# Atlas.net
KiCad netlist of a schematic drawn in EAGLE
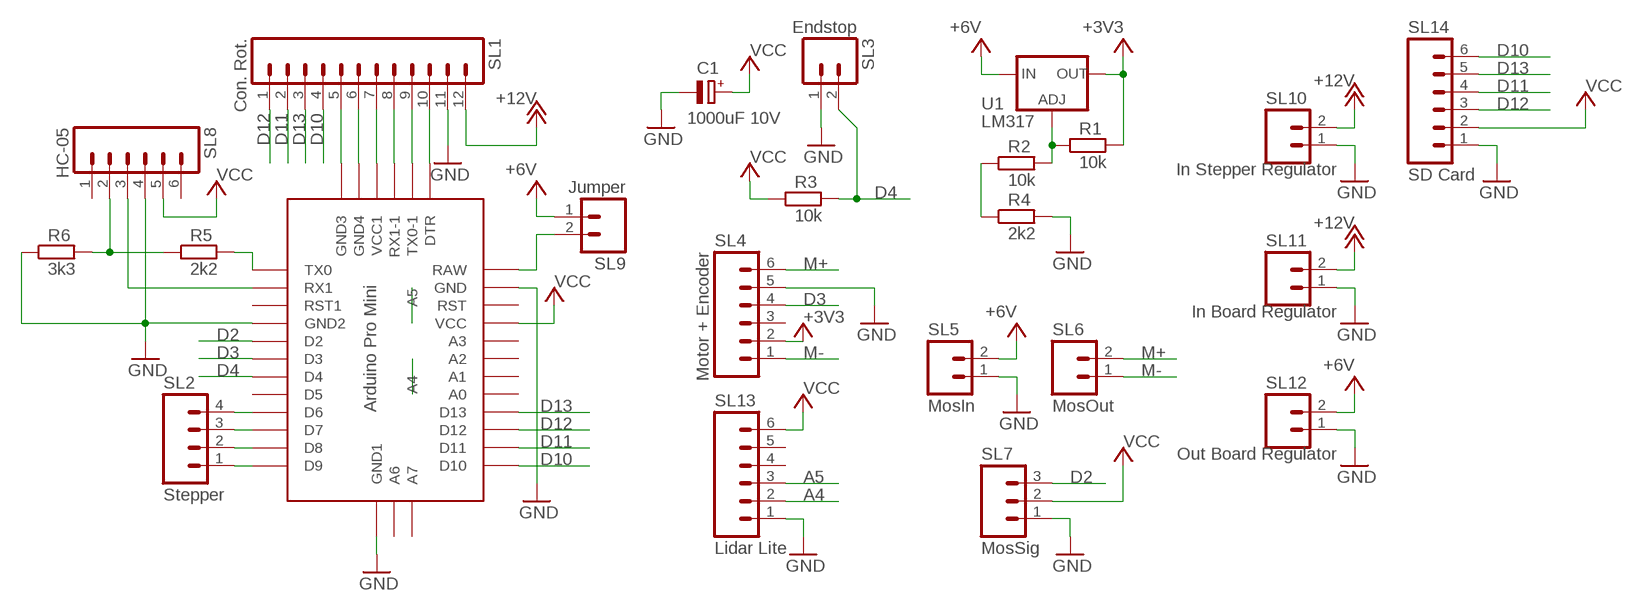
[diagram p0: schematic, sheet 1]

(export (version "E")
  (design (tool "Eeschema 10.0.6"))
  (components
    (comp (ref "C1")
      (value "1000uF 10V")
      (footprint "eagle-import:E5-10,5")
      (libsource (lib "eagle-import") (part "CPOL-EUE5-10.5"))
    )
    (comp (ref "R1")
      (value "10k")
      (footprint "eagle-import:0207_10")
      (libsource (lib "eagle-import") (part "R-EU_0207/10"))
    )
    (comp (ref "R2")
      (value "10k")
      (footprint "eagle-import:0207_10")
      (libsource (lib "eagle-import") (part "R-EU_0207/10"))
    )
    (comp (ref "R3")
      (value "10k")
      (footprint "eagle-import:0207_10")
      (libsource (lib "eagle-import") (part "R-EU_0207/10"))
    )
    (comp (ref "R4")
      (value "2k2")
      (footprint "eagle-import:0207_10")
      (libsource (lib "eagle-import") (part "R-EU_0207/10"))
    )
    (comp (ref "R5")
      (value "2k2")
      (footprint "eagle-import:0207_10")
      (libsource (lib "eagle-import") (part "R-EU_0207/10"))
    )
    (comp (ref "R6")
      (value "3k3")
      (footprint "eagle-import:0207_10")
      (libsource (lib "eagle-import") (part "R-EU_0207/10"))
    )
    (comp (ref "SL1")
      (value "Con. Rot.")
      (footprint "eagle-import:12P")
      (libsource (lib "eagle-import") (part "M12"))
    )
    (comp (ref "SL2")
      (value "Stepper")
      (footprint "eagle-import:04P")
      (libsource (lib "eagle-import") (part "M04"))
    )
    (comp (ref "SL3")
      (value "Endstop")
      (footprint "eagle-import:02P")
      (libsource (lib "eagle-import") (part "M02"))
    )
    (comp (ref "SL4")
      (value "Motor + Encoder")
      (footprint "eagle-import:06P")
      (libsource (lib "eagle-import") (part "M06"))
    )
    (comp (ref "SL5")
      (value "MosIn")
      (footprint "eagle-import:02P")
      (libsource (lib "eagle-import") (part "M02"))
    )
    (comp (ref "SL6")
      (value "MosOut")
      (footprint "eagle-import:02P")
      (libsource (lib "eagle-import") (part "M02"))
    )
    (comp (ref "SL7")
      (value "MosSig")
      (footprint "eagle-import:03P")
      (libsource (lib "eagle-import") (part "M03"))
    )
    (comp (ref "SL8")
      (value "HC-05")
      (footprint "eagle-import:06P")
      (libsource (lib "eagle-import") (part "M06"))
    )
    (comp (ref "SL9")
      (value "Jumper")
      (footprint "eagle-import:02P")
      (libsource (lib "eagle-import") (part "M02"))
    )
    (comp (ref "SL10")
      (value "In Stepper Regulator")
      (footprint "eagle-import:02P")
      (libsource (lib "eagle-import") (part "M02"))
    )
    (comp (ref "SL11")
      (value "In Board Regulator")
      (footprint "eagle-import:02P")
      (libsource (lib "eagle-import") (part "M02"))
    )
    (comp (ref "SL12")
      (value "Out Board Regulator")
      (footprint "eagle-import:02P")
      (libsource (lib "eagle-import") (part "M02"))
    )
    (comp (ref "SL13")
      (value "Lidar Lite")
      (footprint "eagle-import:06P")
      (libsource (lib "eagle-import") (part "M06"))
    )
    (comp (ref "SL14")
      (value "SD Card")
      (footprint "eagle-import:06P")
      (libsource (lib "eagle-import") (part "M06"))
    )
    (comp (ref "U$1")
      (value "ABK-PRO-MINI")
      (footprint "eagle-import:ABK-PRO-MINI")
      (libsource (lib "eagle-import") (part "ABK-PRO-MINI"))
    )
    (comp (ref "U1")
      (value "LM317")
      (footprint "eagle-import:TO220-ADJ")
      (libsource (lib "eagle-import") (part "V_REG_317SINK"))
    )
  )
  (nets
    (net (code "1") (name "+3V3") (class "Default")
      (node (ref "R1") (pin "2") (pinfunction "2_2") (pintype "passive"))
      (node (ref "SL4") (pin "2") (pinfunction "2_2") (pintype "passive"))
      (node (ref "U1") (pin "OUT") (pinfunction "OUT_OUT") (pintype "output"))
    )
    (net (code "2") (name "+6V") (class "Default")
      (node (ref "SL12") (pin "2") (pinfunction "2_2") (pintype "passive"))
      (node (ref "SL5") (pin "2") (pinfunction "2_2") (pintype "passive"))
      (node (ref "SL9") (pin "1") (pinfunction "1_1") (pintype "passive"))
      (node (ref "U1") (pin "IN") (pinfunction "IN_IN") (pintype "input"))
    )
    (net (code "3") (name "+12V") (class "Default")
      (node (ref "SL1") (pin "12") (pinfunction "12_12") (pintype "passive"))
      (node (ref "SL10") (pin "2") (pinfunction "2_2") (pintype "passive"))
      (node (ref "SL11") (pin "2") (pinfunction "2_2") (pintype "passive"))
    )
    (net (code "4") (name "/A4") (class "Default")
      (node (ref "SL13") (pin "2") (pinfunction "2_2") (pintype "passive"))
      (node (ref "U$1") (pin "A4") (pinfunction "A4_A4") (pintype "bidirectional"))
    )
    (net (code "5") (name "/A5") (class "Default")
      (node (ref "SL13") (pin "3") (pinfunction "3_3") (pintype "passive"))
      (node (ref "U$1") (pin "A5") (pinfunction "A5_A5") (pintype "bidirectional"))
    )
    (net (code "6") (name "/D2") (class "Default")
      (node (ref "SL7") (pin "3") (pinfunction "3_3") (pintype "passive"))
      (node (ref "U$1") (pin "D2") (pinfunction "D2_D2") (pintype "bidirectional"))
    )
    (net (code "7") (name "/D3") (class "Default")
      (node (ref "SL4") (pin "4") (pinfunction "4_4") (pintype "passive"))
      (node (ref "U$1") (pin "D3") (pinfunction "D3_D3") (pintype "bidirectional"))
    )
    (net (code "8") (name "/D4") (class "Default")
      (node (ref "R3") (pin "2") (pinfunction "2_2") (pintype "passive"))
      (node (ref "SL3") (pin "2") (pinfunction "2_2") (pintype "passive"))
      (node (ref "U$1") (pin "D4") (pinfunction "D4_D4") (pintype "bidirectional"))
    )
    (net (code "9") (name "/D10") (class "Default")
      (node (ref "SL1") (pin "4") (pinfunction "4_4") (pintype "passive"))
      (node (ref "SL14") (pin "6") (pinfunction "6_6") (pintype "passive"))
      (node (ref "U$1") (pin "D10") (pinfunction "D10_D10") (pintype "bidirectional"))
    )
    (net (code "10") (name "/D11") (class "Default")
      (node (ref "SL1") (pin "2") (pinfunction "2_2") (pintype "passive"))
      (node (ref "SL14") (pin "4") (pinfunction "4_4") (pintype "passive"))
      (node (ref "U$1") (pin "D11") (pinfunction "D11_D11") (pintype "bidirectional"))
    )
    (net (code "11") (name "/D12") (class "Default")
      (node (ref "SL1") (pin "1") (pinfunction "1_1") (pintype "passive"))
      (node (ref "SL14") (pin "3") (pinfunction "3_3") (pintype "passive"))
      (node (ref "U$1") (pin "D12") (pinfunction "D12_D12") (pintype "bidirectional"))
    )
    (net (code "12") (name "/D13") (class "Default")
      (node (ref "SL1") (pin "3") (pinfunction "3_3") (pintype "passive"))
      (node (ref "SL14") (pin "5") (pinfunction "5_5") (pintype "passive"))
      (node (ref "U$1") (pin "D13") (pinfunction "D13_D13") (pintype "bidirectional"))
    )
    (net (code "13") (name "/M+") (class "Default")
      (node (ref "SL4") (pin "6") (pinfunction "6_6") (pintype "passive"))
      (node (ref "SL6") (pin "2") (pinfunction "2_2") (pintype "passive"))
    )
    (net (code "14") (name "/M-") (class "Default")
      (node (ref "SL4") (pin "1") (pinfunction "1_1") (pintype "passive"))
      (node (ref "SL6") (pin "1") (pinfunction "1_1") (pintype "passive"))
    )
    (net (code "15") (name "GND") (class "Default")
      (node (ref "C1") (pin "-") (pinfunction "-_-") (pintype "passive"))
      (node (ref "R4") (pin "2") (pinfunction "2_2") (pintype "passive"))
      (node (ref "R6") (pin "1") (pinfunction "1_1") (pintype "passive"))
      (node (ref "SL1") (pin "11") (pinfunction "11_11") (pintype "passive"))
      (node (ref "SL1") (pin "5") (pinfunction "5_5") (pintype "passive"))
      (node (ref "SL1") (pin "6") (pinfunction "6_6") (pintype "passive"))
      (node (ref "SL10") (pin "1") (pinfunction "1_1") (pintype "passive"))
      (node (ref "SL11") (pin "1") (pinfunction "1_1") (pintype "passive"))
      (node (ref "SL12") (pin "1") (pinfunction "1_1") (pintype "passive"))
      (node (ref "SL13") (pin "1") (pinfunction "1_1") (pintype "passive"))
      (node (ref "SL14") (pin "1") (pinfunction "1_1") (pintype "passive"))
      (node (ref "SL3") (pin "1") (pinfunction "1_1") (pintype "passive"))
      (node (ref "SL4") (pin "5") (pinfunction "5_5") (pintype "passive"))
      (node (ref "SL5") (pin "1") (pinfunction "1_1") (pintype "passive"))
      (node (ref "SL7") (pin "1") (pinfunction "1_1") (pintype "passive"))
      (node (ref "SL8") (pin "4") (pinfunction "4_4") (pintype "passive"))
      (node (ref "U$1") (pin "GND") (pinfunction "GND_GND") (pintype "bidirectional"))
      (node (ref "U$1") (pin "GND1") (pinfunction "GND2_GND1") (pintype "bidirectional"))
      (node (ref "U$1") (pin "GND2") (pinfunction "GND3_GND2") (pintype "bidirectional"))
      (node (ref "U$1") (pin "GND3") (pinfunction "GND4_GND3") (pintype "bidirectional"))
      (node (ref "U$1") (pin "GND4") (pinfunction "GND1_GND4") (pintype "bidirectional"))
    )
    (net (code "16") (name "Net-(R1-Pad1)") (class "Default")
      (node (ref "R1") (pin "1") (pinfunction "1_1") (pintype "passive"))
      (node (ref "R2") (pin "2") (pinfunction "2_2") (pintype "passive"))
      (node (ref "U1") (pin "ADJ") (pinfunction "ADJ_ADJ") (pintype "input"))
    )
    (net (code "17") (name "Net-(R2-Pad1)") (class "Default")
      (node (ref "R2") (pin "1") (pinfunction "1_1") (pintype "passive"))
      (node (ref "R4") (pin "1") (pinfunction "1_1") (pintype "passive"))
    )
    (net (code "18") (name "Net-(R5-Pad1)") (class "Default")
      (node (ref "R5") (pin "1") (pinfunction "1_1") (pintype "passive"))
      (node (ref "R6") (pin "2") (pinfunction "2_2") (pintype "passive"))
      (node (ref "SL8") (pin "2") (pinfunction "2_2") (pintype "passive"))
    )
    (net (code "19") (name "Net-(R5-Pad2)") (class "Default")
      (node (ref "R5") (pin "2") (pinfunction "2_2") (pintype "passive"))
      (node (ref "U$1") (pin "TX0") (pinfunction "TX0_TX0") (pintype "bidirectional"))
    )
    (net (code "20") (name "Net-(SL1-Pad8)") (class "Default")
      (node (ref "SL1") (pin "8") (pinfunction "8_8") (pintype "passive"))
      (node (ref "U$1") (pin "RX1-1") (pinfunction "RX1-1_RX1-1") (pintype "bidirectional"))
    )
    (net (code "21") (name "Net-(SL1-Pad9)") (class "Default")
      (node (ref "SL1") (pin "9") (pinfunction "9_9") (pintype "passive"))
      (node (ref "U$1") (pin "TX0-1") (pinfunction "TX0-1_TX0-1") (pintype "bidirectional"))
    )
    (net (code "22") (name "Net-(SL1-Pad10)") (class "Default")
      (node (ref "SL1") (pin "10") (pinfunction "10_10") (pintype "passive"))
      (node (ref "U$1") (pin "DTR") (pinfunction "DTR_DTR") (pintype "bidirectional"))
    )
    (net (code "23") (name "Net-(SL2-Pad1)") (class "Default")
      (node (ref "SL2") (pin "1") (pinfunction "1_1") (pintype "passive"))
      (node (ref "U$1") (pin "D9") (pinfunction "D9_D9") (pintype "bidirectional"))
    )
    (net (code "24") (name "Net-(SL2-Pad2)") (class "Default")
      (node (ref "SL2") (pin "2") (pinfunction "2_2") (pintype "passive"))
      (node (ref "U$1") (pin "D8") (pinfunction "D8_D8") (pintype "bidirectional"))
    )
    (net (code "25") (name "Net-(SL2-Pad3)") (class "Default")
      (node (ref "SL2") (pin "3") (pinfunction "3_3") (pintype "passive"))
      (node (ref "U$1") (pin "D7") (pinfunction "D7_D7") (pintype "bidirectional"))
    )
    (net (code "26") (name "Net-(SL2-Pad4)") (class "Default")
      (node (ref "SL2") (pin "4") (pinfunction "4_4") (pintype "passive"))
      (node (ref "U$1") (pin "D6") (pinfunction "D6_D6") (pintype "bidirectional"))
    )
    (net (code "27") (name "Net-(SL8-Pad3)") (class "Default")
      (node (ref "SL8") (pin "3") (pinfunction "3_3") (pintype "passive"))
      (node (ref "U$1") (pin "RX1") (pinfunction "RX1_RX1") (pintype "bidirectional"))
    )
    (net (code "28") (name "Net-(SL9-Pad2)") (class "Default")
      (node (ref "SL9") (pin "2") (pinfunction "2_2") (pintype "passive"))
      (node (ref "U$1") (pin "RAW") (pinfunction "RAW_RAW") (pintype "bidirectional"))
    )
    (net (code "29") (name "VCC") (class "Default")
      (node (ref "C1") (pin "+") (pinfunction "+_+") (pintype "passive"))
      (node (ref "R3") (pin "1") (pinfunction "1_1") (pintype "passive"))
      (node (ref "SL1") (pin "7") (pinfunction "7_7") (pintype "passive"))
      (node (ref "SL13") (pin "6") (pinfunction "6_6") (pintype "passive"))
      (node (ref "SL14") (pin "2") (pinfunction "2_2") (pintype "passive"))
      (node (ref "SL7") (pin "2") (pinfunction "2_2") (pintype "passive"))
      (node (ref "SL8") (pin "5") (pinfunction "5_5") (pintype "passive"))
      (node (ref "U$1") (pin "VCC") (pinfunction "VCC_VCC") (pintype "bidirectional"))
      (node (ref "U$1") (pin "VCC1") (pinfunction "VCC1_VCC1") (pintype "bidirectional"))
    )
    (net (code "30") (name "unconnected-(SL4-Pad3)") (class "Default")
      (node (ref "SL4") (pin "3") (pinfunction "3_3") (pintype "passive"))
    )
    (net (code "31") (name "unconnected-(SL8-Pad1)") (class "Default")
      (node (ref "SL8") (pin "1") (pinfunction "1_1") (pintype "passive"))
    )
    (net (code "32") (name "unconnected-(SL8-Pad6)") (class "Default")
      (node (ref "SL8") (pin "6") (pinfunction "6_6") (pintype "passive"))
    )
    (net (code "33") (name "unconnected-(SL13-Pad4)") (class "Default")
      (node (ref "SL13") (pin "4") (pinfunction "4_4") (pintype "passive"))
    )
    (net (code "34") (name "unconnected-(SL13-Pad5)") (class "Default")
      (node (ref "SL13") (pin "5") (pinfunction "5_5") (pintype "passive"))
    )
    (net (code "35") (name "unconnected-(U$1-PadA0)") (class "Default")
      (node (ref "U$1") (pin "A0") (pinfunction "A0_A0") (pintype "bidirectional"))
    )
    (net (code "36") (name "unconnected-(U$1-PadA1)") (class "Default")
      (node (ref "U$1") (pin "A1") (pinfunction "A1_A1") (pintype "bidirectional"))
    )
    (net (code "37") (name "unconnected-(U$1-PadA2)") (class "Default")
      (node (ref "U$1") (pin "A2") (pinfunction "A2_A2") (pintype "bidirectional"))
    )
    (net (code "38") (name "unconnected-(U$1-PadA3)") (class "Default")
      (node (ref "U$1") (pin "A3") (pinfunction "A3_A3") (pintype "bidirectional"))
    )
    (net (code "39") (name "unconnected-(U$1-PadA6)") (class "Default")
      (node (ref "U$1") (pin "A6") (pinfunction "A6_A6") (pintype "bidirectional"))
    )
    (net (code "40") (name "unconnected-(U$1-PadA7)") (class "Default")
      (node (ref "U$1") (pin "A7") (pinfunction "A7_A7") (pintype "bidirectional"))
    )
    (net (code "41") (name "unconnected-(U$1-PadD5)") (class "Default")
      (node (ref "U$1") (pin "D5") (pinfunction "D5_D5") (pintype "bidirectional"))
    )
    (net (code "42") (name "unconnected-(U$1-PadRST)") (class "Default")
      (node (ref "U$1") (pin "RST") (pinfunction "RST_RST") (pintype "bidirectional"))
    )
    (net (code "43") (name "unconnected-(U$1-PadRST1)") (class "Default")
      (node (ref "U$1") (pin "RST1") (pinfunction "RST1_RST1") (pintype "bidirectional"))
    )
  )
)
